# Central_Hub.net
KiCad netlist of a schematic drawn in EAGLE
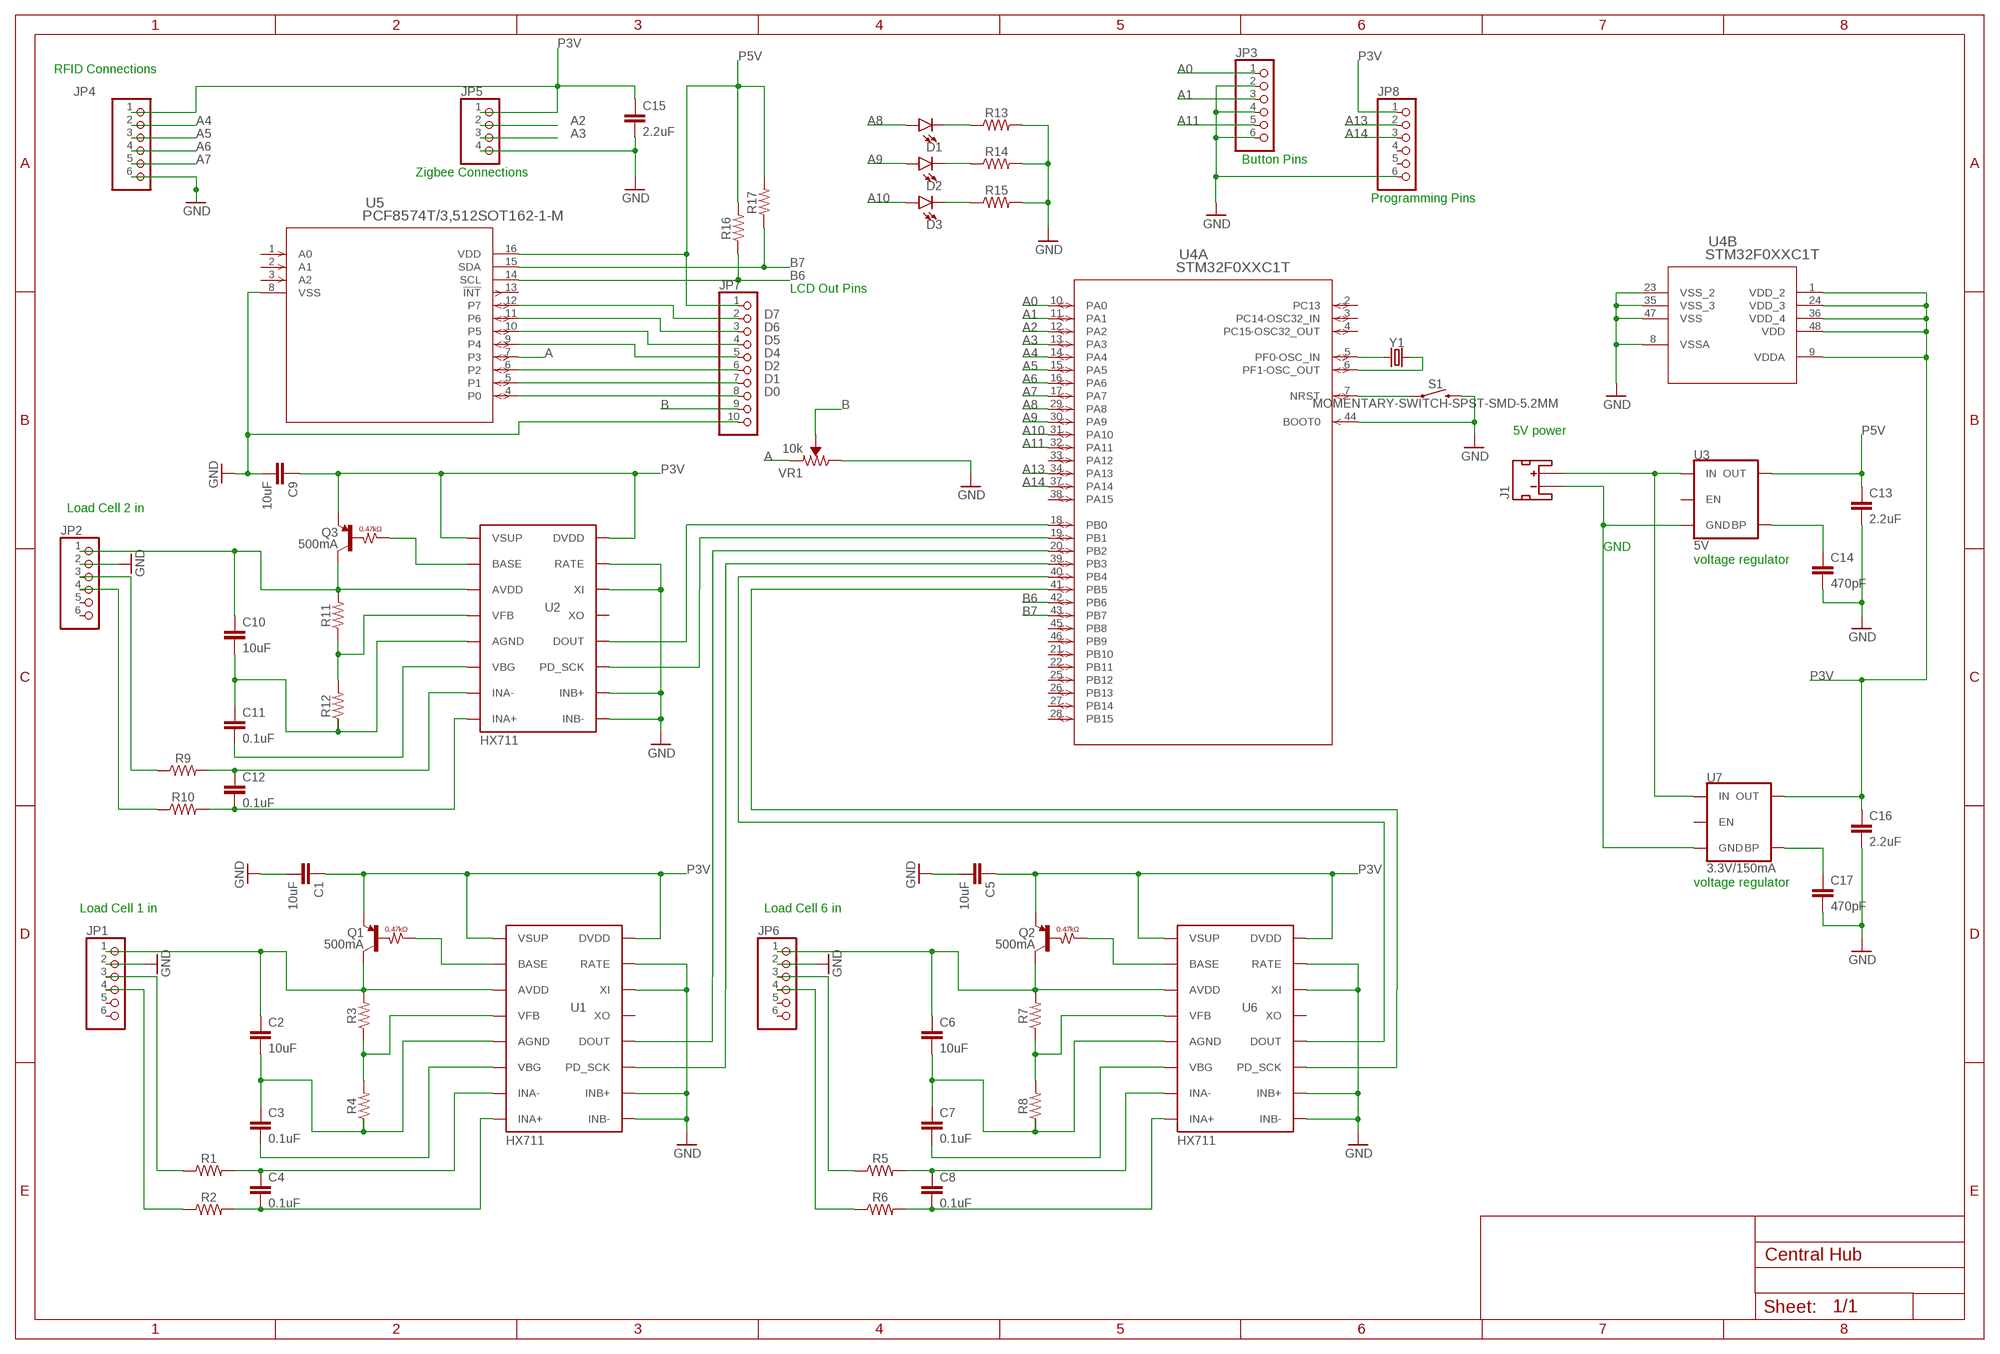
[diagram p0: schematic, sheet 1]

(export (version "E")
  (design (tool "Eeschema 10.0.6"))
  (components
    (comp (ref "C1")
      (value "10uF")
      (footprint "eagle-import:0603")
      (libsource (lib "eagle-import") (part "10UF-0603-6.3V-20%"))
    )
    (comp (ref "C2")
      (value "10uF")
      (footprint "eagle-import:0603")
      (libsource (lib "eagle-import") (part "10UF-0603-6.3V-20%"))
    )
    (comp (ref "C3")
      (value "0.1uF")
      (footprint "eagle-import:0603")
      (libsource (lib "eagle-import") (part "0.1UF-0603-25V-(+80/-20%)"))
    )
    (comp (ref "C4")
      (value "0.1uF")
      (footprint "eagle-import:0603")
      (libsource (lib "eagle-import") (part "0.1UF-0603-25V-(+80/-20%)"))
    )
    (comp (ref "C5")
      (value "10uF")
      (footprint "eagle-import:0603")
      (libsource (lib "eagle-import") (part "10UF-0603-6.3V-20%"))
    )
    (comp (ref "C6")
      (value "10uF")
      (footprint "eagle-import:0603")
      (libsource (lib "eagle-import") (part "10UF-0603-6.3V-20%"))
    )
    (comp (ref "C7")
      (value "0.1uF")
      (footprint "eagle-import:0603")
      (libsource (lib "eagle-import") (part "0.1UF-0603-25V-(+80/-20%)"))
    )
    (comp (ref "C8")
      (value "0.1uF")
      (footprint "eagle-import:0603")
      (libsource (lib "eagle-import") (part "0.1UF-0603-25V-(+80/-20%)"))
    )
    (comp (ref "C9")
      (value "10uF")
      (footprint "eagle-import:0603")
      (libsource (lib "eagle-import") (part "10UF-0603-6.3V-20%"))
    )
    (comp (ref "C10")
      (value "10uF")
      (footprint "eagle-import:0603")
      (libsource (lib "eagle-import") (part "10UF-0603-6.3V-20%"))
    )
    (comp (ref "C11")
      (value "0.1uF")
      (footprint "eagle-import:0603")
      (libsource (lib "eagle-import") (part "0.1UF-0603-25V-(+80/-20%)"))
    )
    (comp (ref "C12")
      (value "0.1uF")
      (footprint "eagle-import:0603")
      (libsource (lib "eagle-import") (part "0.1UF-0603-25V-(+80/-20%)"))
    )
    (comp (ref "C13")
      (value "2.2uF")
      (footprint "eagle-import:0603")
      (libsource (lib "eagle-import") (part "2.2UF-0603-10V-20%"))
    )
    (comp (ref "C14")
      (value "470pF")
      (footprint "eagle-import:0603")
      (libsource (lib "eagle-import") (part "470PF-0603-50V-5%"))
    )
    (comp (ref "C15")
      (value "2.2uF")
      (footprint "eagle-import:0603")
      (libsource (lib "eagle-import") (part "2.2UF-0603-10V-20%"))
    )
    (comp (ref "C16")
      (value "2.2uF")
      (footprint "eagle-import:0603")
      (libsource (lib "eagle-import") (part "2.2UF-0603-10V-20%"))
    )
    (comp (ref "C17")
      (value "470pF")
      (footprint "eagle-import:0603")
      (libsource (lib "eagle-import") (part "470PF-0603-50V-5%"))
    )
    (comp (ref "D1")
      (value "LED5MM")
      (footprint "eagle-import:LED_5MM")
      (libsource (lib "eagle-import") (part "LED5MM"))
    )
    (comp (ref "D2")
      (value "LED5MM")
      (footprint "eagle-import:LED_5MM")
      (libsource (lib "eagle-import") (part "LED5MM"))
    )
    (comp (ref "D3")
      (value "LED5MM")
      (footprint "eagle-import:LED_5MM")
      (libsource (lib "eagle-import") (part "LED5MM"))
    )
    (comp (ref "J1")
      (value "JST_2MM_MALE")
      (footprint "eagle-import:JST-2-SMD")
      (libsource (lib "eagle-import") (part "JST_2MM_MALE"))
    )
    (comp (ref "JP1")
      (value "PINHD-1X6")
      (footprint "eagle-import:1X06")
      (libsource (lib "eagle-import") (part "PINHD-1X6"))
    )
    (comp (ref "JP2")
      (value "PINHD-1X6")
      (footprint "eagle-import:1X06")
      (libsource (lib "eagle-import") (part "PINHD-1X6"))
    )
    (comp (ref "JP3")
      (value "PINHD-1X6")
      (footprint "eagle-import:1X06")
      (libsource (lib "eagle-import") (part "PINHD-1X6"))
    )
    (comp (ref "JP4")
      (value "PINHD-1X6")
      (footprint "eagle-import:1X06")
      (libsource (lib "eagle-import") (part "PINHD-1X6"))
    )
    (comp (ref "JP5")
      (value "PINHD-1X4")
      (footprint "eagle-import:1X04")
      (libsource (lib "eagle-import") (part "PINHD-1X4"))
    )
    (comp (ref "JP6")
      (value "PINHD-1X6")
      (footprint "eagle-import:1X06")
      (libsource (lib "eagle-import") (part "PINHD-1X6"))
    )
    (comp (ref "JP7")
      (value "PINHD-1X10")
      (footprint "eagle-import:1X10")
      (libsource (lib "eagle-import") (part "PINHD-1X10"))
    )
    (comp (ref "JP8")
      (value "PINHD-1X6")
      (footprint "eagle-import:1X06")
      (libsource (lib "eagle-import") (part "PINHD-1X6"))
    )
    (comp (ref "Q1")
      (value "500mA")
      (footprint "eagle-import:SOT23-3")
      (libsource (lib "eagle-import") (part "TRANS_PNP_RES-DDTB142TC"))
    )
    (comp (ref "Q2")
      (value "500mA")
      (footprint "eagle-import:SOT23-3")
      (libsource (lib "eagle-import") (part "TRANS_PNP_RES-DDTB142TC"))
    )
    (comp (ref "Q3")
      (value "500mA")
      (footprint "eagle-import:SOT23-3")
      (libsource (lib "eagle-import") (part "TRANS_PNP_RES-DDTB142TC"))
    )
    (comp (ref "R1")
      (value "RESISTOR0603")
      (footprint "eagle-import:0603")
      (libsource (lib "eagle-import") (part "RESISTOR0603"))
    )
    (comp (ref "R2")
      (value "RESISTOR0603")
      (footprint "eagle-import:0603")
      (libsource (lib "eagle-import") (part "RESISTOR0603"))
    )
    (comp (ref "R3")
      (value "RESISTOR0603")
      (footprint "eagle-import:0603")
      (libsource (lib "eagle-import") (part "RESISTOR0603"))
    )
    (comp (ref "R4")
      (value "RESISTOR0603")
      (footprint "eagle-import:0603")
      (libsource (lib "eagle-import") (part "RESISTOR0603"))
    )
    (comp (ref "R5")
      (value "RESISTOR0603")
      (footprint "eagle-import:0603")
      (libsource (lib "eagle-import") (part "RESISTOR0603"))
    )
    (comp (ref "R6")
      (value "RESISTOR0603")
      (footprint "eagle-import:0603")
      (libsource (lib "eagle-import") (part "RESISTOR0603"))
    )
    (comp (ref "R7")
      (value "RESISTOR0603")
      (footprint "eagle-import:0603")
      (libsource (lib "eagle-import") (part "RESISTOR0603"))
    )
    (comp (ref "R8")
      (value "RESISTOR0603")
      (footprint "eagle-import:0603")
      (libsource (lib "eagle-import") (part "RESISTOR0603"))
    )
    (comp (ref "R9")
      (value "RESISTOR0603")
      (footprint "eagle-import:0603")
      (libsource (lib "eagle-import") (part "RESISTOR0603"))
    )
    (comp (ref "R10")
      (value "RESISTOR0603")
      (footprint "eagle-import:0603")
      (libsource (lib "eagle-import") (part "RESISTOR0603"))
    )
    (comp (ref "R11")
      (value "RESISTOR0603")
      (footprint "eagle-import:0603")
      (libsource (lib "eagle-import") (part "RESISTOR0603"))
    )
    (comp (ref "R12")
      (value "RESISTOR0603")
      (footprint "eagle-import:0603")
      (libsource (lib "eagle-import") (part "RESISTOR0603"))
    )
    (comp (ref "R13")
      (value "RESISTOR0603")
      (footprint "eagle-import:0603")
      (libsource (lib "eagle-import") (part "RESISTOR0603"))
    )
    (comp (ref "R14")
      (value "RESISTOR0603")
      (footprint "eagle-import:0603")
      (libsource (lib "eagle-import") (part "RESISTOR0603"))
    )
    (comp (ref "R15")
      (value "RESISTOR0603")
      (footprint "eagle-import:0603")
      (libsource (lib "eagle-import") (part "RESISTOR0603"))
    )
    (comp (ref "R16")
      (value "RESISTOR0603")
      (footprint "eagle-import:0603")
      (libsource (lib "eagle-import") (part "RESISTOR0603"))
    )
    (comp (ref "R17")
      (value "RESISTOR0603")
      (footprint "eagle-import:0603")
      (libsource (lib "eagle-import") (part "RESISTOR0603"))
    )
    (comp (ref "S1")
      (value "MOMENTARY-SWITCH-SPST-SMD-5.2MM")
      (footprint "eagle-import:TACTILE_SWITCH_SMD_5.2MM")
      (libsource (lib "eagle-import") (part "MOMENTARY-SWITCH-SPST-SMD-5.2MM"))
    )
    (comp (ref "U1")
      (value "HX711")
      (footprint "eagle-import:SO16")
      (libsource (lib "eagle-import") (part "HX711"))
    )
    (comp (ref "U2")
      (value "HX711")
      (footprint "eagle-import:SO16")
      (libsource (lib "eagle-import") (part "HX711"))
    )
    (comp (ref "U3")
      (value "5V")
      (footprint "eagle-import:SOT23-5")
      (libsource (lib "eagle-import") (part "V_REG_MIC52055V"))
    )
    (comp (ref "U4")
      (value "STM32F0XXC1T")
      (footprint "eagle-import:LQFP48-7X7MM")
      (fields (field (name "MANUFACTURER_PART_NUMBER") "stm32f0xxc1t"))
      (libsource (lib "eagle-import") (part "STM32F0XXC1T"))
    )
    (comp (ref "U5")
      (value "PCF8574T/3,512SOT162-1-M")
      (footprint "eagle-import:SOT162-1-M")
      (fields (field (name "MANUFACTURER_PART_NUMBER") "PCF8574T3512"))
      (libsource (lib "eagle-import") (part "PCF8574T/3,512SOT162-1-M"))
    )
    (comp (ref "U6")
      (value "HX711")
      (footprint "eagle-import:SO16")
      (libsource (lib "eagle-import") (part "HX711"))
    )
    (comp (ref "U7")
      (value "3.3V/150mA")
      (footprint "eagle-import:SOT23-5")
      (libsource (lib "eagle-import") (part "V_REG_MIC52053.3V"))
    )
    (comp (ref "VR1")
      (value "10k")
      (footprint "eagle-import:TRIMPOT-PTH-3386U")
      (libsource (lib "eagle-import") (part "TRIMPOT-PTH-10MM-KNOB-1/2W-10%"))
    )
    (comp (ref "Y1")
      (value "CRYSTALPTH-HC49US")
      (footprint "eagle-import:HC49US")
      (libsource (lib "eagle-import") (part "CRYSTALPTH-HC49US"))
    )
  )
  (nets
    (net (code "1") (name "/A") (class "Default")
      (node (ref "U5") (pin "7") (pinfunction "P3_7") (pintype "bidirectional"))
      (node (ref "VR1") (pin "1") (pinfunction "CCW_1") (pintype "passive"))
    )
    (net (code "2") (name "/A0") (class "Default")
      (node (ref "JP3") (pin "1") (pinfunction "1_1") (pintype "passive"))
      (node (ref "U4") (pin "10") (pinfunction "PA0_10") (pintype "bidirectional"))
    )
    (net (code "3") (name "/A1") (class "Default")
      (node (ref "JP3") (pin "3") (pinfunction "3_3") (pintype "passive"))
      (node (ref "U4") (pin "11") (pinfunction "PA1_11") (pintype "bidirectional"))
    )
    (net (code "4") (name "/A2") (class "Default")
      (node (ref "JP5") (pin "2") (pinfunction "2_2") (pintype "passive"))
      (node (ref "U4") (pin "12") (pinfunction "PA2_12") (pintype "bidirectional"))
    )
    (net (code "5") (name "/A3") (class "Default")
      (node (ref "JP5") (pin "3") (pinfunction "3_3") (pintype "passive"))
      (node (ref "U4") (pin "13") (pinfunction "PA3_13") (pintype "bidirectional"))
    )
    (net (code "6") (name "/A4") (class "Default")
      (node (ref "JP4") (pin "2") (pinfunction "2_2") (pintype "passive"))
      (node (ref "U4") (pin "14") (pinfunction "PA4_14") (pintype "bidirectional"))
    )
    (net (code "7") (name "/A5") (class "Default")
      (node (ref "JP4") (pin "3") (pinfunction "3_3") (pintype "passive"))
      (node (ref "U4") (pin "15") (pinfunction "PA5_15") (pintype "bidirectional"))
    )
    (net (code "8") (name "/A6") (class "Default")
      (node (ref "JP4") (pin "4") (pinfunction "4_4") (pintype "passive"))
      (node (ref "U4") (pin "16") (pinfunction "PA6_16") (pintype "bidirectional"))
    )
    (net (code "9") (name "/A7") (class "Default")
      (node (ref "JP4") (pin "5") (pinfunction "5_5") (pintype "passive"))
      (node (ref "U4") (pin "17") (pinfunction "PA7_17") (pintype "bidirectional"))
    )
    (net (code "10") (name "/A8") (class "Default")
      (node (ref "D1") (pin "A") (pinfunction "A_A") (pintype "passive"))
      (node (ref "U4") (pin "29") (pinfunction "PA8_29") (pintype "bidirectional"))
    )
    (net (code "11") (name "/A9") (class "Default")
      (node (ref "D2") (pin "A") (pinfunction "A_A") (pintype "passive"))
      (node (ref "U4") (pin "30") (pinfunction "PA9_30") (pintype "bidirectional"))
    )
    (net (code "12") (name "/A10") (class "Default")
      (node (ref "D3") (pin "A") (pinfunction "A_A") (pintype "passive"))
      (node (ref "U4") (pin "31") (pinfunction "PA10_31") (pintype "bidirectional"))
    )
    (net (code "13") (name "/A11") (class "Default")
      (node (ref "JP3") (pin "5") (pinfunction "5_5") (pintype "passive"))
      (node (ref "U4") (pin "32") (pinfunction "PA11_32") (pintype "bidirectional"))
    )
    (net (code "14") (name "/A13") (class "Default")
      (node (ref "JP8") (pin "2") (pinfunction "2_2") (pintype "passive"))
      (node (ref "U4") (pin "34") (pinfunction "PA13_34") (pintype "bidirectional"))
    )
    (net (code "15") (name "/A14") (class "Default")
      (node (ref "JP8") (pin "3") (pinfunction "3_3") (pintype "passive"))
      (node (ref "U4") (pin "37") (pinfunction "PA14_37") (pintype "bidirectional"))
    )
    (net (code "16") (name "/B") (class "Default")
      (node (ref "JP7") (pin "9") (pinfunction "9_9") (pintype "passive"))
      (node (ref "VR1") (pin "2") (pinfunction "WIPER_2") (pintype "passive"))
    )
    (net (code "17") (name "/B6") (class "Default")
      (node (ref "R16") (pin "1") (pinfunction "1_1") (pintype "passive"))
      (node (ref "U4") (pin "42") (pinfunction "PB6_42") (pintype "bidirectional"))
      (node (ref "U5") (pin "14") (pinfunction "SCL_14") (pintype "passive"))
    )
    (net (code "18") (name "/B7") (class "Default")
      (node (ref "R17") (pin "1") (pinfunction "1_1") (pintype "passive"))
      (node (ref "U4") (pin "43") (pinfunction "PB7_43") (pintype "bidirectional"))
      (node (ref "U5") (pin "15") (pinfunction "SDA_15") (pintype "passive"))
    )
    (net (code "19") (name "/D0") (class "Default")
      (node (ref "JP7") (pin "8") (pinfunction "8_8") (pintype "passive"))
      (node (ref "U5") (pin "4") (pinfunction "P0_4") (pintype "bidirectional"))
    )
    (net (code "20") (name "/D1") (class "Default")
      (node (ref "JP7") (pin "7") (pinfunction "7_7") (pintype "passive"))
      (node (ref "U5") (pin "5") (pinfunction "P1_5") (pintype "bidirectional"))
    )
    (net (code "21") (name "/D2") (class "Default")
      (node (ref "JP7") (pin "6") (pinfunction "6_6") (pintype "passive"))
      (node (ref "U5") (pin "6") (pinfunction "P2_6") (pintype "bidirectional"))
    )
    (net (code "22") (name "/D4") (class "Default")
      (node (ref "JP7") (pin "5") (pinfunction "5_5") (pintype "passive"))
      (node (ref "U5") (pin "9") (pinfunction "P4_9") (pintype "bidirectional"))
    )
    (net (code "23") (name "/D5") (class "Default")
      (node (ref "JP7") (pin "4") (pinfunction "4_4") (pintype "passive"))
      (node (ref "U5") (pin "10") (pinfunction "P5_10") (pintype "bidirectional"))
    )
    (net (code "24") (name "/D6") (class "Default")
      (node (ref "JP7") (pin "3") (pinfunction "3_3") (pintype "passive"))
      (node (ref "U5") (pin "11") (pinfunction "P6_11") (pintype "bidirectional"))
    )
    (net (code "25") (name "/D7") (class "Default")
      (node (ref "JP7") (pin "2") (pinfunction "2_2") (pintype "passive"))
      (node (ref "U5") (pin "12") (pinfunction "P7_12") (pintype "bidirectional"))
    )
    (net (code "26") (name "/P3V") (class "Default")
      (node (ref "C1") (pin "1") (pinfunction "1_1") (pintype "passive"))
      (node (ref "C15") (pin "1") (pinfunction "1_1") (pintype "passive"))
      (node (ref "C16") (pin "1") (pinfunction "1_1") (pintype "passive"))
      (node (ref "C5") (pin "1") (pinfunction "1_1") (pintype "passive"))
      (node (ref "C9") (pin "1") (pinfunction "1_1") (pintype "passive"))
      (node (ref "JP4") (pin "1") (pinfunction "1_1") (pintype "passive"))
      (node (ref "JP5") (pin "1") (pinfunction "1_1") (pintype "passive"))
      (node (ref "JP8") (pin "1") (pinfunction "1_1") (pintype "passive"))
      (node (ref "Q1") (pin "2") (pinfunction "E_2") (pintype "passive"))
      (node (ref "Q2") (pin "2") (pinfunction "E_2") (pintype "passive"))
      (node (ref "Q3") (pin "2") (pinfunction "E_2") (pintype "passive"))
      (node (ref "U1") (pin "1") (pinfunction "VSUP_1") (pintype "bidirectional"))
      (node (ref "U1") (pin "16") (pinfunction "DVDD_16") (pintype "bidirectional"))
      (node (ref "U2") (pin "1") (pinfunction "VSUP_1") (pintype "bidirectional"))
      (node (ref "U2") (pin "16") (pinfunction "DVDD_16") (pintype "bidirectional"))
      (node (ref "U4") (pin "1") (pinfunction "VDD_2_1") (pintype "power_in"))
      (node (ref "U4") (pin "24") (pinfunction "VDD_3_24") (pintype "power_in"))
      (node (ref "U4") (pin "36") (pinfunction "VDD_4_36") (pintype "power_in"))
      (node (ref "U4") (pin "48") (pinfunction "VDD_48") (pintype "power_in"))
      (node (ref "U4") (pin "9") (pinfunction "VDDA_9") (pintype "power_in"))
      (node (ref "U6") (pin "1") (pinfunction "VSUP_1") (pintype "bidirectional"))
      (node (ref "U6") (pin "16") (pinfunction "DVDD_16") (pintype "bidirectional"))
      (node (ref "U7") (pin "5") (pinfunction "OUT_5") (pintype "passive"))
    )
    (net (code "27") (name "/P5V") (class "Default")
      (node (ref "C13") (pin "1") (pinfunction "1_1") (pintype "passive"))
      (node (ref "JP7") (pin "1") (pinfunction "1_1") (pintype "passive"))
      (node (ref "R16") (pin "2") (pinfunction "2_2") (pintype "passive"))
      (node (ref "R17") (pin "2") (pinfunction "2_2") (pintype "passive"))
      (node (ref "U3") (pin "5") (pinfunction "OUT_5") (pintype "passive"))
      (node (ref "U5") (pin "16") (pinfunction "VDD_16") (pintype "power_in"))
    )
    (net (code "28") (name "GND") (class "Default")
      (node (ref "C1") (pin "2") (pinfunction "2_2") (pintype "passive"))
      (node (ref "C13") (pin "2") (pinfunction "2_2") (pintype "passive"))
      (node (ref "C14") (pin "2") (pinfunction "2_2") (pintype "passive"))
      (node (ref "C15") (pin "2") (pinfunction "2_2") (pintype "passive"))
      (node (ref "C16") (pin "2") (pinfunction "2_2") (pintype "passive"))
      (node (ref "C17") (pin "2") (pinfunction "2_2") (pintype "passive"))
      (node (ref "C5") (pin "2") (pinfunction "2_2") (pintype "passive"))
      (node (ref "C9") (pin "2") (pinfunction "2_2") (pintype "passive"))
      (node (ref "JP1") (pin "2") (pinfunction "2_2") (pintype "passive"))
      (node (ref "JP2") (pin "2") (pinfunction "2_2") (pintype "passive"))
      (node (ref "JP3") (pin "2") (pinfunction "2_2") (pintype "passive"))
      (node (ref "JP3") (pin "4") (pinfunction "4_4") (pintype "passive"))
      (node (ref "JP3") (pin "6") (pinfunction "6_6") (pintype "passive"))
      (node (ref "JP4") (pin "6") (pinfunction "6_6") (pintype "passive"))
      (node (ref "JP5") (pin "4") (pinfunction "4_4") (pintype "passive"))
      (node (ref "JP6") (pin "2") (pinfunction "2_2") (pintype "passive"))
      (node (ref "JP7") (pin "10") (pinfunction "10_10") (pintype "passive"))
      (node (ref "JP8") (pin "6") (pinfunction "6_6") (pintype "passive"))
      (node (ref "R13") (pin "2") (pinfunction "2_2") (pintype "passive"))
      (node (ref "R14") (pin "2") (pinfunction "2_2") (pintype "passive"))
      (node (ref "R15") (pin "2") (pinfunction "2_2") (pintype "passive"))
      (node (ref "S1") (pin "3") (pinfunction "2_3") (pintype "passive"))
      (node (ref "U1") (pin "10") (pinfunction "INB+_10") (pintype "bidirectional"))
      (node (ref "U1") (pin "14") (pinfunction "XI_14") (pintype "bidirectional"))
      (node (ref "U1") (pin "15") (pinfunction "RATE_15") (pintype "bidirectional"))
      (node (ref "U1") (pin "9") (pinfunction "INB-_9") (pintype "bidirectional"))
      (node (ref "U2") (pin "10") (pinfunction "INB+_10") (pintype "bidirectional"))
      (node (ref "U2") (pin "14") (pinfunction "XI_14") (pintype "bidirectional"))
      (node (ref "U2") (pin "15") (pinfunction "RATE_15") (pintype "bidirectional"))
      (node (ref "U2") (pin "9") (pinfunction "INB-_9") (pintype "bidirectional"))
      (node (ref "U4") (pin "23") (pinfunction "VSS_2_23") (pintype "power_in"))
      (node (ref "U4") (pin "35") (pinfunction "VSS_3_35") (pintype "power_in"))
      (node (ref "U4") (pin "44") (pinfunction "BOOT0_44") (pintype "input"))
      (node (ref "U4") (pin "47") (pinfunction "VSS_47") (pintype "power_in"))
      (node (ref "U4") (pin "8") (pinfunction "VSSA_8") (pintype "power_in"))
      (node (ref "U5") (pin "8") (pinfunction "VSS_8") (pintype "power_in"))
      (node (ref "U6") (pin "10") (pinfunction "INB+_10") (pintype "bidirectional"))
      (node (ref "U6") (pin "14") (pinfunction "XI_14") (pintype "bidirectional"))
      (node (ref "U6") (pin "15") (pinfunction "RATE_15") (pintype "bidirectional"))
      (node (ref "U6") (pin "9") (pinfunction "INB-_9") (pintype "bidirectional"))
      (node (ref "VR1") (pin "3") (pinfunction "CW_3") (pintype "passive"))
    )
    (net (code "29") (name "Net-(D1-C)") (class "Default")
      (node (ref "D1") (pin "K") (pinfunction "C_K") (pintype "passive"))
      (node (ref "R13") (pin "1") (pinfunction "1_1") (pintype "passive"))
    )
    (net (code "30") (name "Net-(D2-C)") (class "Default")
      (node (ref "D2") (pin "K") (pinfunction "C_K") (pintype "passive"))
      (node (ref "R14") (pin "1") (pinfunction "1_1") (pintype "passive"))
    )
    (net (code "31") (name "Net-(D3-C)") (class "Default")
      (node (ref "D3") (pin "K") (pinfunction "C_K") (pintype "passive"))
      (node (ref "R15") (pin "1") (pinfunction "1_1") (pintype "passive"))
    )
    (net (code "32") (name "Net-(J1-+)") (class "Default")
      (node (ref "J1") (pin "2") (pinfunction "+_2") (pintype "bidirectional"))
      (node (ref "U3") (pin "1") (pinfunction "IN_1") (pintype "input"))
      (node (ref "U7") (pin "1") (pinfunction "IN_1") (pintype "input"))
    )
    (net (code "33") (name "Net-(J1--)") (class "Default")
      (node (ref "J1") (pin "1") (pinfunction "-_1") (pintype "bidirectional"))
      (node (ref "U3") (pin "2") (pinfunction "GND_2") (pintype "input"))
      (node (ref "U7") (pin "2") (pinfunction "GND_2") (pintype "input"))
    )
    (net (code "34") (name "Net-(JP1-Pad3)") (class "Default")
      (node (ref "JP1") (pin "3") (pinfunction "3_3") (pintype "passive"))
      (node (ref "R1") (pin "1") (pinfunction "1_1") (pintype "passive"))
    )
    (net (code "35") (name "Net-(JP1-Pad4)") (class "Default")
      (node (ref "JP1") (pin "4") (pinfunction "4_4") (pintype "passive"))
      (node (ref "R2") (pin "1") (pinfunction "1_1") (pintype "passive"))
    )
    (net (code "36") (name "Net-(JP2-Pad3)") (class "Default")
      (node (ref "JP2") (pin "3") (pinfunction "3_3") (pintype "passive"))
      (node (ref "R9") (pin "1") (pinfunction "1_1") (pintype "passive"))
    )
    (net (code "37") (name "Net-(JP2-Pad4)") (class "Default")
      (node (ref "JP2") (pin "4") (pinfunction "4_4") (pintype "passive"))
      (node (ref "R10") (pin "1") (pinfunction "1_1") (pintype "passive"))
    )
    (net (code "38") (name "Net-(JP6-Pad3)") (class "Default")
      (node (ref "JP6") (pin "3") (pinfunction "3_3") (pintype "passive"))
      (node (ref "R5") (pin "1") (pinfunction "1_1") (pintype "passive"))
    )
    (net (code "39") (name "Net-(JP6-Pad4)") (class "Default")
      (node (ref "JP6") (pin "4") (pinfunction "4_4") (pintype "passive"))
      (node (ref "R6") (pin "1") (pinfunction "1_1") (pintype "passive"))
    )
    (net (code "40") (name "Net-(Q1-B)") (class "Default")
      (node (ref "Q1") (pin "1") (pinfunction "B_1") (pintype "passive"))
      (node (ref "U1") (pin "2") (pinfunction "BASE_2") (pintype "bidirectional"))
    )
    (net (code "41") (name "Net-(Q1-C)") (class "Default")
      (node (ref "C2") (pin "1") (pinfunction "1_1") (pintype "passive"))
      (node (ref "JP1") (pin "1") (pinfunction "1_1") (pintype "passive"))
      (node (ref "Q1") (pin "3") (pinfunction "C_3") (pintype "passive"))
      (node (ref "R3") (pin "2") (pinfunction "2_2") (pintype "passive"))
      (node (ref "U1") (pin "3") (pinfunction "AVDD_3") (pintype "bidirectional"))
    )
    (net (code "42") (name "Net-(Q2-B)") (class "Default")
      (node (ref "Q2") (pin "1") (pinfunction "B_1") (pintype "passive"))
      (node (ref "U6") (pin "2") (pinfunction "BASE_2") (pintype "bidirectional"))
    )
    (net (code "43") (name "Net-(Q2-C)") (class "Default")
      (node (ref "C6") (pin "1") (pinfunction "1_1") (pintype "passive"))
      (node (ref "JP6") (pin "1") (pinfunction "1_1") (pintype "passive"))
      (node (ref "Q2") (pin "3") (pinfunction "C_3") (pintype "passive"))
      (node (ref "R7") (pin "2") (pinfunction "2_2") (pintype "passive"))
      (node (ref "U6") (pin "3") (pinfunction "AVDD_3") (pintype "bidirectional"))
    )
    (net (code "44") (name "Net-(Q3-B)") (class "Default")
      (node (ref "Q3") (pin "1") (pinfunction "B_1") (pintype "passive"))
      (node (ref "U2") (pin "2") (pinfunction "BASE_2") (pintype "bidirectional"))
    )
    (net (code "45") (name "Net-(Q3-C)") (class "Default")
      (node (ref "C10") (pin "1") (pinfunction "1_1") (pintype "passive"))
      (node (ref "JP2") (pin "1") (pinfunction "1_1") (pintype "passive"))
      (node (ref "Q3") (pin "3") (pinfunction "C_3") (pintype "passive"))
      (node (ref "R11") (pin "2") (pinfunction "2_2") (pintype "passive"))
      (node (ref "U2") (pin "3") (pinfunction "AVDD_3") (pintype "bidirectional"))
    )
    (net (code "46") (name "Net-(U1-AGND)") (class "Default")
      (node (ref "C2") (pin "2") (pinfunction "2_2") (pintype "passive"))
      (node (ref "C3") (pin "1") (pinfunction "1_1") (pintype "passive"))
      (node (ref "R4") (pin "1") (pinfunction "1_1") (pintype "passive"))
      (node (ref "U1") (pin "5") (pinfunction "AGND_5") (pintype "bidirectional"))
    )
    (net (code "47") (name "Net-(U1-DOUT)") (class "Default")
      (node (ref "U1") (pin "12") (pinfunction "DOUT_12") (pintype "bidirectional"))
      (node (ref "U4") (pin "20") (pinfunction "PB2_20") (pintype "bidirectional"))
    )
    (net (code "48") (name "Net-(U1-INA+)") (class "Default")
      (node (ref "C4") (pin "2") (pinfunction "2_2") (pintype "passive"))
      (node (ref "R2") (pin "2") (pinfunction "2_2") (pintype "passive"))
      (node (ref "U1") (pin "8") (pinfunction "INA+_8") (pintype "bidirectional"))
    )
    (net (code "49") (name "Net-(U1-INA-)") (class "Default")
      (node (ref "C4") (pin "1") (pinfunction "1_1") (pintype "passive"))
      (node (ref "R1") (pin "2") (pinfunction "2_2") (pintype "passive"))
      (node (ref "U1") (pin "7") (pinfunction "INA-_7") (pintype "bidirectional"))
    )
    (net (code "50") (name "Net-(U1-PD_SCK)") (class "Default")
      (node (ref "U1") (pin "11") (pinfunction "PD_SCK_11") (pintype "bidirectional"))
      (node (ref "U4") (pin "39") (pinfunction "PB3_39") (pintype "bidirectional"))
    )
    (net (code "51") (name "Net-(U1-VBG)") (class "Default")
      (node (ref "C3") (pin "2") (pinfunction "2_2") (pintype "passive"))
      (node (ref "U1") (pin "6") (pinfunction "VBG_6") (pintype "bidirectional"))
    )
    (net (code "52") (name "Net-(U1-VFB)") (class "Default")
      (node (ref "R3") (pin "1") (pinfunction "1_1") (pintype "passive"))
      (node (ref "R4") (pin "2") (pinfunction "2_2") (pintype "passive"))
      (node (ref "U1") (pin "4") (pinfunction "VFB_4") (pintype "bidirectional"))
    )
    (net (code "53") (name "Net-(U2-AGND)") (class "Default")
      (node (ref "C10") (pin "2") (pinfunction "2_2") (pintype "passive"))
      (node (ref "C11") (pin "1") (pinfunction "1_1") (pintype "passive"))
      (node (ref "R12") (pin "1") (pinfunction "1_1") (pintype "passive"))
      (node (ref "U2") (pin "5") (pinfunction "AGND_5") (pintype "bidirectional"))
    )
    (net (code "54") (name "Net-(U2-DOUT)") (class "Default")
      (node (ref "U2") (pin "12") (pinfunction "DOUT_12") (pintype "bidirectional"))
      (node (ref "U4") (pin "18") (pinfunction "PB0_18") (pintype "bidirectional"))
    )
    (net (code "55") (name "Net-(U2-INA+)") (class "Default")
      (node (ref "C12") (pin "2") (pinfunction "2_2") (pintype "passive"))
      (node (ref "R10") (pin "2") (pinfunction "2_2") (pintype "passive"))
      (node (ref "U2") (pin "8") (pinfunction "INA+_8") (pintype "bidirectional"))
    )
    (net (code "56") (name "Net-(U2-INA-)") (class "Default")
      (node (ref "C12") (pin "1") (pinfunction "1_1") (pintype "passive"))
      (node (ref "R9") (pin "2") (pinfunction "2_2") (pintype "passive"))
      (node (ref "U2") (pin "7") (pinfunction "INA-_7") (pintype "bidirectional"))
    )
    (net (code "57") (name "Net-(U2-PD_SCK)") (class "Default")
      (node (ref "U2") (pin "11") (pinfunction "PD_SCK_11") (pintype "bidirectional"))
      (node (ref "U4") (pin "19") (pinfunction "PB1_19") (pintype "bidirectional"))
    )
    (net (code "58") (name "Net-(U2-VBG)") (class "Default")
      (node (ref "C11") (pin "2") (pinfunction "2_2") (pintype "passive"))
      (node (ref "U2") (pin "6") (pinfunction "VBG_6") (pintype "bidirectional"))
    )
    (net (code "59") (name "Net-(U2-VFB)") (class "Default")
      (node (ref "R11") (pin "1") (pinfunction "1_1") (pintype "passive"))
      (node (ref "R12") (pin "2") (pinfunction "2_2") (pintype "passive"))
      (node (ref "U2") (pin "4") (pinfunction "VFB_4") (pintype "bidirectional"))
    )
    (net (code "60") (name "Net-(U3-BP)") (class "Default")
      (node (ref "C14") (pin "1") (pinfunction "1_1") (pintype "passive"))
      (node (ref "U3") (pin "4") (pinfunction "BP_4") (pintype "input"))
    )
    (net (code "61") (name "Net-(U4A-NRST)") (class "Default")
      (node (ref "S1") (pin "1") (pinfunction "1_1") (pintype "passive"))
      (node (ref "U4") (pin "7") (pinfunction "NRST_7") (pintype "bidirectional"))
    )
    (net (code "62") (name "Net-(U4A-PB4)") (class "Default")
      (node (ref "U4") (pin "40") (pinfunction "PB4_40") (pintype "bidirectional"))
      (node (ref "U6") (pin "12") (pinfunction "DOUT_12") (pintype "bidirectional"))
    )
    (net (code "63") (name "Net-(U4A-PB5)") (class "Default")
      (node (ref "U4") (pin "41") (pinfunction "PB5_41") (pintype "bidirectional"))
      (node (ref "U6") (pin "11") (pinfunction "PD_SCK_11") (pintype "bidirectional"))
    )
    (net (code "64") (name "Net-(U4A-PF0-OSC_IN)") (class "Default")
      (node (ref "U4") (pin "5") (pinfunction "PF0-OSC_IN_5") (pintype "bidirectional"))
      (node (ref "Y1") (pin "1") (pinfunction "1_1") (pintype "passive"))
    )
    (net (code "65") (name "Net-(U4A-PF1-OSC_OUT)") (class "Default")
      (node (ref "U4") (pin "6") (pinfunction "PF1-OSC_OUT_6") (pintype "bidirectional"))
      (node (ref "Y1") (pin "2") (pinfunction "2_2") (pintype "passive"))
    )
    (net (code "66") (name "Net-(U6-AGND)") (class "Default")
      (node (ref "C6") (pin "2") (pinfunction "2_2") (pintype "passive"))
      (node (ref "C7") (pin "1") (pinfunction "1_1") (pintype "passive"))
      (node (ref "R8") (pin "1") (pinfunction "1_1") (pintype "passive"))
      (node (ref "U6") (pin "5") (pinfunction "AGND_5") (pintype "bidirectional"))
    )
    (net (code "67") (name "Net-(U6-INA+)") (class "Default")
      (node (ref "C8") (pin "2") (pinfunction "2_2") (pintype "passive"))
      (node (ref "R6") (pin "2") (pinfunction "2_2") (pintype "passive"))
      (node (ref "U6") (pin "8") (pinfunction "INA+_8") (pintype "bidirectional"))
    )
    (net (code "68") (name "Net-(U6-INA-)") (class "Default")
      (node (ref "C8") (pin "1") (pinfunction "1_1") (pintype "passive"))
      (node (ref "R5") (pin "2") (pinfunction "2_2") (pintype "passive"))
      (node (ref "U6") (pin "7") (pinfunction "INA-_7") (pintype "bidirectional"))
    )
    (net (code "69") (name "Net-(U6-VBG)") (class "Default")
      (node (ref "C7") (pin "2") (pinfunction "2_2") (pintype "passive"))
      (node (ref "U6") (pin "6") (pinfunction "VBG_6") (pintype "bidirectional"))
    )
    (net (code "70") (name "Net-(U6-VFB)") (class "Default")
      (node (ref "R7") (pin "1") (pinfunction "1_1") (pintype "passive"))
      (node (ref "R8") (pin "2") (pinfunction "2_2") (pintype "passive"))
      (node (ref "U6") (pin "4") (pinfunction "VFB_4") (pintype "bidirectional"))
    )
    (net (code "71") (name "Net-(U7-BP)") (class "Default")
      (node (ref "C17") (pin "1") (pinfunction "1_1") (pintype "passive"))
      (node (ref "U7") (pin "4") (pinfunction "BP_4") (pintype "input"))
    )
    (net (code "72") (name "unconnected-(J1-PAD1-PadNC1)") (class "Default")
      (node (ref "J1") (pin "NC1") (pinfunction "PAD1_NC1") (pintype "bidirectional"))
    )
    (net (code "73") (name "unconnected-(J1-PAD2-PadNC2)") (class "Default")
      (node (ref "J1") (pin "NC2") (pinfunction "PAD2_NC2") (pintype "bidirectional"))
    )
    (net (code "74") (name "unconnected-(JP1-Pad5)") (class "Default")
      (node (ref "JP1") (pin "5") (pinfunction "5_5") (pintype "passive"))
    )
    (net (code "75") (name "unconnected-(JP1-Pad6)") (class "Default")
      (node (ref "JP1") (pin "6") (pinfunction "6_6") (pintype "passive"))
    )
    (net (code "76") (name "unconnected-(JP2-Pad5)") (class "Default")
      (node (ref "JP2") (pin "5") (pinfunction "5_5") (pintype "passive"))
    )
    (net (code "77") (name "unconnected-(JP2-Pad6)") (class "Default")
      (node (ref "JP2") (pin "6") (pinfunction "6_6") (pintype "passive"))
    )
    (net (code "78") (name "unconnected-(JP6-Pad5)") (class "Default")
      (node (ref "JP6") (pin "5") (pinfunction "5_5") (pintype "passive"))
    )
    (net (code "79") (name "unconnected-(JP6-Pad6)") (class "Default")
      (node (ref "JP6") (pin "6") (pinfunction "6_6") (pintype "passive"))
    )
    (net (code "80") (name "unconnected-(JP8-Pad4)") (class "Default")
      (node (ref "JP8") (pin "4") (pinfunction "4_4") (pintype "passive"))
    )
    (net (code "81") (name "unconnected-(JP8-Pad5)") (class "Default")
      (node (ref "JP8") (pin "5") (pinfunction "5_5") (pintype "passive"))
    )
    (net (code "82") (name "unconnected-(U1-XO-Pad13)") (class "Default")
      (node (ref "U1") (pin "13") (pinfunction "XO_13") (pintype "bidirectional"))
    )
    (net (code "83") (name "unconnected-(U2-XO-Pad13)") (class "Default")
      (node (ref "U2") (pin "13") (pinfunction "XO_13") (pintype "bidirectional"))
    )
    (net (code "84") (name "unconnected-(U3-EN-Pad3)") (class "Default")
      (node (ref "U3") (pin "3") (pinfunction "EN_3") (pintype "input"))
    )
    (net (code "85") (name "unconnected-(U4A-PA12-Pad33)") (class "Default")
      (node (ref "U4") (pin "33") (pinfunction "PA12_33") (pintype "bidirectional"))
    )
    (net (code "86") (name "unconnected-(U4A-PA15-Pad38)") (class "Default")
      (node (ref "U4") (pin "38") (pinfunction "PA15_38") (pintype "bidirectional"))
    )
    (net (code "87") (name "unconnected-(U4A-PB8-Pad45)") (class "Default")
      (node (ref "U4") (pin "45") (pinfunction "PB8_45") (pintype "bidirectional"))
    )
    (net (code "88") (name "unconnected-(U4A-PB9-Pad46)") (class "Default")
      (node (ref "U4") (pin "46") (pinfunction "PB9_46") (pintype "bidirectional"))
    )
    (net (code "89") (name "unconnected-(U4A-PB10-Pad21)") (class "Default")
      (node (ref "U4") (pin "21") (pinfunction "PB10_21") (pintype "bidirectional"))
    )
    (net (code "90") (name "unconnected-(U4A-PB11-Pad22)") (class "Default")
      (node (ref "U4") (pin "22") (pinfunction "PB11_22") (pintype "bidirectional"))
    )
    (net (code "91") (name "unconnected-(U4A-PB12-Pad25)") (class "Default")
      (node (ref "U4") (pin "25") (pinfunction "PB12_25") (pintype "bidirectional"))
    )
    (net (code "92") (name "unconnected-(U4A-PB13-Pad26)") (class "Default")
      (node (ref "U4") (pin "26") (pinfunction "PB13_26") (pintype "bidirectional"))
    )
    (net (code "93") (name "unconnected-(U4A-PB14-Pad27)") (class "Default")
      (node (ref "U4") (pin "27") (pinfunction "PB14_27") (pintype "bidirectional"))
    )
    (net (code "94") (name "unconnected-(U4A-PB15-Pad28)") (class "Default")
      (node (ref "U4") (pin "28") (pinfunction "PB15_28") (pintype "bidirectional"))
    )
    (net (code "95") (name "unconnected-(U4A-PC13-Pad2)") (class "Default")
      (node (ref "U4") (pin "2") (pinfunction "PC13_2") (pintype "bidirectional"))
    )
    (net (code "96") (name "unconnected-(U4A-PC14-OSC32_IN-Pad3)") (class "Default")
      (node (ref "U4") (pin "3") (pinfunction "PC14-OSC32_IN_3") (pintype "bidirectional"))
    )
    (net (code "97") (name "unconnected-(U4A-PC15-OSC32_OUT-Pad4)") (class "Default")
      (node (ref "U4") (pin "4") (pinfunction "PC15-OSC32_OUT_4") (pintype "bidirectional"))
    )
    (net (code "98") (name "unconnected-(U5-A0-Pad1)") (class "Default")
      (node (ref "U5") (pin "1") (pinfunction "A0_1") (pintype "input"))
    )
    (net (code "99") (name "unconnected-(U5-A1-Pad2)") (class "Default")
      (node (ref "U5") (pin "2") (pinfunction "A1_2") (pintype "input"))
    )
    (net (code "100") (name "unconnected-(U5-A2-Pad3)") (class "Default")
      (node (ref "U5") (pin "3") (pinfunction "A2_3") (pintype "input"))
    )
    (net (code "101") (name "unconnected-(U5-~{INT}-Pad13)") (class "Default")
      (node (ref "U5") (pin "13") (pinfunction "~{INT}_13") (pintype "output"))
    )
    (net (code "102") (name "unconnected-(U6-XO-Pad13)") (class "Default")
      (node (ref "U6") (pin "13") (pinfunction "XO_13") (pintype "bidirectional"))
    )
    (net (code "103") (name "unconnected-(U7-EN-Pad3)") (class "Default")
      (node (ref "U7") (pin "3") (pinfunction "EN_3") (pintype "input"))
    )
  )
)
